# ControlVoltage.net
KiCad netlist of a schematic drawn in Altium Designer
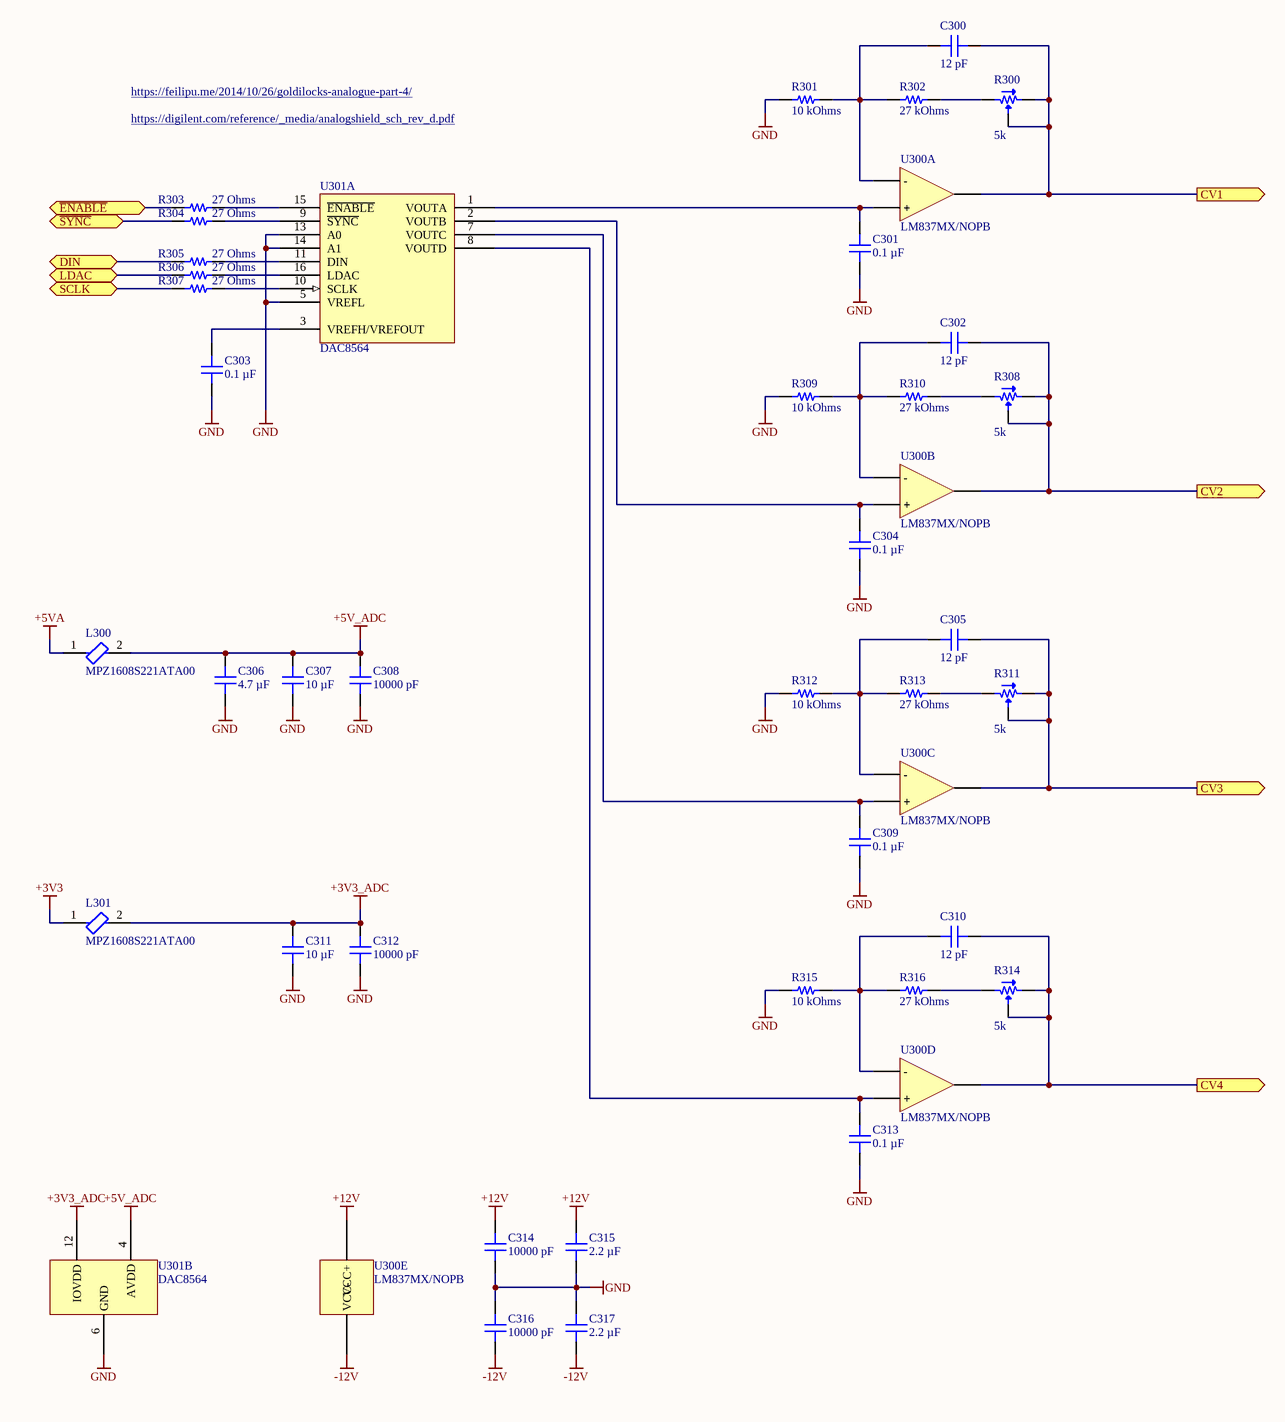
[diagram p0: ControlVoltage.SchDoc]

(export (version "E")
  (design (tool "Eeschema 10.0.6"))
  (components
    (comp (ref "C300")
      (value "12 pF")
      (footprint "CAP 0603_1608")
      (description "CAP CER 12PF 50V C0G/NPO 0603")
      (fields (field (name "PART NUMBER") "CC0603KRNPO9BN120") (field (name "MANUFACTURER") "Yageo"))
      (libsource (lib "Celestial Altium Library") (part "Capacitor"))
    )
    (comp (ref "C301")
      (value "0.1 µF")
      (footprint "CAP 0603_1608")
      (description "CAP CER 0.1UF 16V X7R 0603")
      (fields (field (name "PART NUMBER") "CS0603KRX7R7BB104") (field (name "MANUFACTURER") "Yageo"))
      (libsource (lib "Celestial Altium Library") (part "Capacitor"))
    )
    (comp (ref "C302")
      (value "12 pF")
      (footprint "CAP 0603_1608")
      (description "CAP CER 12PF 50V C0G/NPO 0603")
      (fields (field (name "PART NUMBER") "CC0603KRNPO9BN120") (field (name "MANUFACTURER") "Yageo"))
      (libsource (lib "Celestial Altium Library") (part "Capacitor"))
    )
    (comp (ref "C303")
      (value "0.1 µF")
      (footprint "CAP 0603_1608")
      (description "CAP CER 0.1UF 25V Y5V 0603")
      (fields (field (name "PART NUMBER") "CC0603MRY5V8BB104") (field (name "MANUFACTURER") "Yageo"))
      (libsource (lib "Celestial Altium Library") (part "Capacitor"))
    )
    (comp (ref "C304")
      (value "0.1 µF")
      (footprint "CAP 0603_1608")
      (description "CAP CER 0.1UF 16V X7R 0603")
      (fields (field (name "PART NUMBER") "CS0603KRX7R7BB104") (field (name "MANUFACTURER") "Yageo"))
      (libsource (lib "Celestial Altium Library") (part "Capacitor"))
    )
    (comp (ref "C305")
      (value "12 pF")
      (footprint "CAP 0603_1608")
      (description "CAP CER 12PF 50V C0G/NPO 0603")
      (fields (field (name "PART NUMBER") "CC0603KRNPO9BN120") (field (name "MANUFACTURER") "Yageo"))
      (libsource (lib "Celestial Altium Library") (part "Capacitor"))
    )
    (comp (ref "C306")
      (value "4.7 µF")
      (footprint "CAP 0603_1608")
      (description "CAP CER 4.7UF 10V X5R 0603")
      (fields (field (name "PART NUMBER") "CC0603MRX5R6BB475") (field (name "MANUFACTURER") "Yageo"))
      (libsource (lib "Celestial Altium Library") (part "Capacitor"))
    )
    (comp (ref "C307")
      (value "10 µF")
      (footprint "CAP 0603_1608")
      (description "CAP CER 10UF 4V X5R 0603")
      (fields (field (name "PART NUMBER") "CC0603MRX5R4BB106") (field (name "MANUFACTURER") "Yageo"))
      (libsource (lib "Celestial Altium Library") (part "Capacitor"))
    )
    (comp (ref "C308")
      (value "10000 pF")
      (footprint "CAP 0603_1608")
      (description "CAP CER 10000PF 50V X7R 0603")
      (fields (field (name "PART NUMBER") "CC0603JRX7R9BB103") (field (name "MANUFACTURER") "Yageo"))
      (libsource (lib "Celestial Altium Library") (part "Capacitor"))
    )
    (comp (ref "C309")
      (value "0.1 µF")
      (footprint "CAP 0603_1608")
      (description "CAP CER 0.1UF 16V X7R 0603")
      (fields (field (name "PART NUMBER") "CS0603KRX7R7BB104") (field (name "MANUFACTURER") "Yageo"))
      (libsource (lib "Celestial Altium Library") (part "Capacitor"))
    )
    (comp (ref "C310")
      (value "12 pF")
      (footprint "CAP 0603_1608")
      (description "CAP CER 12PF 50V C0G/NPO 0603")
      (fields (field (name "PART NUMBER") "CC0603KRNPO9BN120") (field (name "MANUFACTURER") "Yageo"))
      (libsource (lib "Celestial Altium Library") (part "Capacitor"))
    )
    (comp (ref "C311")
      (value "10 µF")
      (footprint "CAP 0603_1608")
      (description "CAP CER 10UF 4V X5R 0603")
      (fields (field (name "PART NUMBER") "CC0603MRX5R4BB106") (field (name "MANUFACTURER") "Yageo"))
      (libsource (lib "Celestial Altium Library") (part "Capacitor"))
    )
    (comp (ref "C312")
      (value "10000 pF")
      (footprint "CAP 0603_1608")
      (description "CAP CER 10000PF 50V X7R 0603")
      (fields (field (name "PART NUMBER") "CC0603JRX7R9BB103") (field (name "MANUFACTURER") "Yageo"))
      (libsource (lib "Celestial Altium Library") (part "Capacitor"))
    )
    (comp (ref "C313")
      (value "0.1 µF")
      (footprint "CAP 0603_1608")
      (description "CAP CER 0.1UF 16V X7R 0603")
      (fields (field (name "PART NUMBER") "CS0603KRX7R7BB104") (field (name "MANUFACTURER") "Yageo"))
      (libsource (lib "Celestial Altium Library") (part "Capacitor"))
    )
    (comp (ref "C314")
      (value "10000 pF")
      (footprint "CAP 0603_1608")
      (description "CAP CER 10000PF 50V X7R 0603")
      (fields (field (name "PART NUMBER") "CC0603JRX7R9BB103") (field (name "MANUFACTURER") "Yageo"))
      (libsource (lib "Celestial Altium Library") (part "Capacitor"))
    )
    (comp (ref "C315")
      (value "2.2 µF")
      (footprint "CAP 0603_1608")
      (description "CAP CER 2.2UF 16V Y5V 0603")
      (fields (field (name "PART NUMBER") "CC0603ZRY5V7BB225") (field (name "MANUFACTURER") "Yageo"))
      (libsource (lib "Celestial Altium Library") (part "Capacitor"))
    )
    (comp (ref "C316")
      (value "10000 pF")
      (footprint "CAP 0603_1608")
      (description "CAP CER 10000PF 50V X7R 0603")
      (fields (field (name "PART NUMBER") "CC0603JRX7R9BB103") (field (name "MANUFACTURER") "Yageo"))
      (libsource (lib "Celestial Altium Library") (part "Capacitor"))
    )
    (comp (ref "C317")
      (value "2.2 µF")
      (footprint "CAP 0603_1608")
      (description "CAP CER 2.2UF 16V Y5V 0603")
      (fields (field (name "PART NUMBER") "CC0603ZRY5V7BB225") (field (name "MANUFACTURER") "Yageo"))
      (libsource (lib "Celestial Altium Library") (part "Capacitor"))
    )
    (comp (ref "L300")
      (value "MPZ1608S221ATA00")
      (footprint "FP-MPZ1608-0_8-MFG")
      (description "Power line Ferrite Bead 220Ω @ 100MHz 2.2A DCR 0.05Ω SMD 0603")
      (fields (field (name "TOLERANCE") "25%"))
      (libsource (lib "Altium Content Vault") (part "5f30dd21d616792df468990f7003faa"))
    )
    (comp (ref "L301")
      (value "MPZ1608S221ATA00")
      (footprint "FP-MPZ1608-0_8-MFG")
      (description "Power line Ferrite Bead 220Ω @ 100MHz 2.2A DCR 0.05Ω SMD 0603")
      (fields (field (name "TOLERANCE") "25%"))
      (libsource (lib "Altium Content Vault") (part "5f30dd21d616792df468990f7003faa"))
    )
    (comp (ref "R300")
      (value "5k")
      (footprint "BOURNS_TRIM_3296")
      (description "Bourns Trimmer Resistor - Through Hole - Series 3296")
      (libsource (lib "LabratsSynthLib") (part "BOURNS_TRIM_POT_3296"))
    )
    (comp (ref "R301")
      (value "10 kOhms")
      (footprint "RES 0603_1608")
      (description "RES SMD 10K OHM 1% 1/10W 0603")
      (fields (field (name "PART NUMBER") "CRCW060310K0FKTA") (field (name "MANUFACTURER") "Vishay Dale"))
      (libsource (lib "Celestial Altium Library") (part "Resistor"))
    )
    (comp (ref "R302")
      (value "27 kOhms")
      (footprint "RES 0603_1608")
      (description "RES 24.9K OHM 1% 1/10W 0603")
      (fields (field (name "PART NUMBER") "CRCW060324K9FKEAC") (field (name "MANUFACTURER") "Vishay Dale"))
      (libsource (lib "Celestial Altium Library") (part "Resistor"))
    )
    (comp (ref "R303")
      (value "27 Ohms")
      (footprint "RES 0603_1608")
      (description "RES SMD 27 OHM 1% 1/10W 0603")
      (fields (field (name "PART NUMBER") "CRCW060327R0FKEA") (field (name "MANUFACTURER") "Vishay Dale"))
      (libsource (lib "Celestial Altium Library") (part "Resistor"))
    )
    (comp (ref "R304")
      (value "27 Ohms")
      (footprint "RES 0603_1608")
      (description "RES SMD 27 OHM 1% 1/10W 0603")
      (fields (field (name "PART NUMBER") "CRCW060327R0FKEA") (field (name "MANUFACTURER") "Vishay Dale"))
      (libsource (lib "Celestial Altium Library") (part "Resistor"))
    )
    (comp (ref "R305")
      (value "27 Ohms")
      (footprint "RES 0603_1608")
      (description "RES SMD 27 OHM 1% 1/10W 0603")
      (fields (field (name "PART NUMBER") "CRCW060327R0FKEA") (field (name "MANUFACTURER") "Vishay Dale"))
      (libsource (lib "Celestial Altium Library") (part "Resistor"))
    )
    (comp (ref "R306")
      (value "27 Ohms")
      (footprint "RES 0603_1608")
      (description "RES SMD 27 OHM 1% 1/10W 0603")
      (fields (field (name "PART NUMBER") "CRCW060327R0FKEA") (field (name "MANUFACTURER") "Vishay Dale"))
      (libsource (lib "Celestial Altium Library") (part "Resistor"))
    )
    (comp (ref "R307")
      (value "27 Ohms")
      (footprint "RES 0603_1608")
      (description "RES SMD 27 OHM 1% 1/10W 0603")
      (fields (field (name "PART NUMBER") "CRCW060327R0FKEA") (field (name "MANUFACTURER") "Vishay Dale"))
      (libsource (lib "Celestial Altium Library") (part "Resistor"))
    )
    (comp (ref "R308")
      (value "5k")
      (footprint "BOURNS_TRIM_3296")
      (description "Bourns Trimmer Resistor - Through Hole - Series 3296")
      (libsource (lib "LabratsSynthLib") (part "BOURNS_TRIM_POT_3296"))
    )
    (comp (ref "R309")
      (value "10 kOhms")
      (footprint "RES 0603_1608")
      (description "RES SMD 10K OHM 1% 1/10W 0603")
      (fields (field (name "PART NUMBER") "CRCW060310K0FKTA") (field (name "MANUFACTURER") "Vishay Dale"))
      (libsource (lib "Celestial Altium Library") (part "Resistor"))
    )
    (comp (ref "R310")
      (value "27 kOhms")
      (footprint "RES 0603_1608")
      (description "RES 24.9K OHM 1% 1/10W 0603")
      (fields (field (name "PART NUMBER") "CRCW060324K9FKEAC") (field (name "MANUFACTURER") "Vishay Dale"))
      (libsource (lib "Celestial Altium Library") (part "Resistor"))
    )
    (comp (ref "R311")
      (value "5k")
      (footprint "BOURNS_TRIM_3296")
      (description "Bourns Trimmer Resistor - Through Hole - Series 3296")
      (libsource (lib "LabratsSynthLib") (part "BOURNS_TRIM_POT_3296"))
    )
    (comp (ref "R312")
      (value "10 kOhms")
      (footprint "RES 0603_1608")
      (description "RES SMD 10K OHM 1% 1/10W 0603")
      (fields (field (name "PART NUMBER") "CRCW060310K0FKTA") (field (name "MANUFACTURER") "Vishay Dale"))
      (libsource (lib "Celestial Altium Library") (part "Resistor"))
    )
    (comp (ref "R313")
      (value "27 kOhms")
      (footprint "RES 0603_1608")
      (description "RES 24.9K OHM 1% 1/10W 0603")
      (fields (field (name "PART NUMBER") "CRCW060324K9FKEAC") (field (name "MANUFACTURER") "Vishay Dale"))
      (libsource (lib "Celestial Altium Library") (part "Resistor"))
    )
    (comp (ref "R314")
      (value "5k")
      (footprint "BOURNS_TRIM_3296")
      (description "Bourns Trimmer Resistor - Through Hole - Series 3296")
      (libsource (lib "LabratsSynthLib") (part "BOURNS_TRIM_POT_3296"))
    )
    (comp (ref "R315")
      (value "10 kOhms")
      (footprint "RES 0603_1608")
      (description "RES SMD 10K OHM 1% 1/10W 0603")
      (fields (field (name "PART NUMBER") "CRCW060310K0FKTA") (field (name "MANUFACTURER") "Vishay Dale"))
      (libsource (lib "Celestial Altium Library") (part "Resistor"))
    )
    (comp (ref "R316")
      (value "27 kOhms")
      (footprint "RES 0603_1608")
      (description "RES 24.9K OHM 1% 1/10W 0603")
      (fields (field (name "PART NUMBER") "CRCW060324K9FKEAC") (field (name "MANUFACTURER") "Vishay Dale"))
      (libsource (lib "Celestial Altium Library") (part "Resistor"))
    )
    (comp (ref "U300")
      (value "LM837MX/NOPB")
      (footprint "FP-D0014A-IPC_B")
      (description "IC OPAMP GP 4 CIRCUIT 14SOIC")
      (libsource (lib "LabratsSynthLib") (part "LM837MX/NOPB"))
    )
    (comp (ref "U301")
      (value "DAC8564")
      (footprint "SOP65P640X120-16N")
      (description "Digital to Analog Converters - DAC 16B Quad Ch Ultra-Lo Glitch Vltg Output")
      (libsource (lib "LabratsSynthLib") (part "DAC8564"))
    )
  )
  (nets
    (net (code "1") (name "+3V3") (class "Default")
      (node (ref "L301") (pin "1") (pinfunction "1_1") (pintype "passive"))
    )
    (net (code "2") (name "+3V3_ADC") (class "Default")
      (node (ref "C311") (pin "2") (pinfunction "2_2") (pintype "passive"))
      (node (ref "C312") (pin "2") (pinfunction "2_2") (pintype "passive"))
      (node (ref "L301") (pin "2") (pinfunction "2_2") (pintype "passive"))
      (node (ref "U301") (pin "12") (pinfunction "IOVDD_12") (pintype "power_in"))
    )
    (net (code "3") (name "+5VA") (class "Default")
      (node (ref "L300") (pin "1") (pinfunction "1_1") (pintype "passive"))
    )
    (net (code "4") (name "+5V_ADC") (class "Default")
      (node (ref "C306") (pin "2") (pinfunction "2_2") (pintype "passive"))
      (node (ref "C307") (pin "2") (pinfunction "2_2") (pintype "passive"))
      (node (ref "C308") (pin "2") (pinfunction "2_2") (pintype "passive"))
      (node (ref "L300") (pin "2") (pinfunction "2_2") (pintype "passive"))
      (node (ref "U301") (pin "4") (pinfunction "AVDD_4") (pintype "power_in"))
    )
    (net (code "5") (name "+12V") (class "Default")
      (node (ref "C314") (pin "2") (pinfunction "2_2") (pintype "passive"))
      (node (ref "C315") (pin "2") (pinfunction "2_2") (pintype "passive"))
      (node (ref "U300") (pin "4") (pinfunction "VCC+_4") (pintype "power_in"))
    )
    (net (code "6") (name "-12V") (class "Default")
      (node (ref "C316") (pin "1") (pinfunction "1_1") (pintype "passive"))
      (node (ref "C317") (pin "1") (pinfunction "1_1") (pintype "passive"))
      (node (ref "U300") (pin "11") (pinfunction "VCC-_11") (pintype "power_in"))
    )
    (net (code "7") (name "/CV1") (class "Default")
      (node (ref "C300") (pin "2") (pinfunction "2_2") (pintype "passive"))
      (node (ref "R300") (pin "2") (pinfunction "2_2") (pintype "passive"))
      (node (ref "R300") (pin "3") (pinfunction "3_3") (pintype "passive"))
      (node (ref "U300") (pin "1") (pinfunction "Output_1") (pintype "passive"))
    )
    (net (code "8") (name "/CV2") (class "Default")
      (node (ref "C302") (pin "2") (pinfunction "2_2") (pintype "passive"))
      (node (ref "R308") (pin "2") (pinfunction "2_2") (pintype "passive"))
      (node (ref "R308") (pin "3") (pinfunction "3_3") (pintype "passive"))
      (node (ref "U300") (pin "7") (pinfunction "Output_7") (pintype "passive"))
    )
    (net (code "9") (name "/CV3") (class "Default")
      (node (ref "C305") (pin "2") (pinfunction "2_2") (pintype "passive"))
      (node (ref "R311") (pin "2") (pinfunction "2_2") (pintype "passive"))
      (node (ref "R311") (pin "3") (pinfunction "3_3") (pintype "passive"))
      (node (ref "U300") (pin "8") (pinfunction "Output_8") (pintype "passive"))
    )
    (net (code "10") (name "/CV4") (class "Default")
      (node (ref "C310") (pin "2") (pinfunction "2_2") (pintype "passive"))
      (node (ref "R314") (pin "2") (pinfunction "2_2") (pintype "passive"))
      (node (ref "R314") (pin "3") (pinfunction "3_3") (pintype "passive"))
      (node (ref "U300") (pin "14") (pinfunction "Output_14") (pintype "passive"))
    )
    (net (code "11") (name "/DIN") (class "Default")
      (node (ref "R305") (pin "1") (pinfunction "1_1") (pintype "passive"))
    )
    (net (code "12") (name "/LDAC") (class "Default")
      (node (ref "R306") (pin "1") (pinfunction "1_1") (pintype "passive"))
    )
    (net (code "13") (name "/SCLK") (class "Default")
      (node (ref "R307") (pin "1") (pinfunction "1_1") (pintype "passive"))
    )
    (net (code "14") (name "/~{ENABLE}") (class "Default")
      (node (ref "R303") (pin "1") (pinfunction "1_1") (pintype "passive"))
    )
    (net (code "15") (name "/~{SYNC}") (class "Default")
      (node (ref "R304") (pin "1") (pinfunction "1_1") (pintype "passive"))
    )
    (net (code "16") (name "GND") (class "Default")
      (node (ref "C301") (pin "1") (pinfunction "1_1") (pintype "passive"))
      (node (ref "C303") (pin "1") (pinfunction "1_1") (pintype "passive"))
      (node (ref "C304") (pin "1") (pinfunction "1_1") (pintype "passive"))
      (node (ref "C306") (pin "1") (pinfunction "1_1") (pintype "passive"))
      (node (ref "C307") (pin "1") (pinfunction "1_1") (pintype "passive"))
      (node (ref "C308") (pin "1") (pinfunction "1_1") (pintype "passive"))
      (node (ref "C309") (pin "1") (pinfunction "1_1") (pintype "passive"))
      (node (ref "C311") (pin "1") (pinfunction "1_1") (pintype "passive"))
      (node (ref "C312") (pin "1") (pinfunction "1_1") (pintype "passive"))
      (node (ref "C313") (pin "1") (pinfunction "1_1") (pintype "passive"))
      (node (ref "C314") (pin "1") (pinfunction "1_1") (pintype "passive"))
      (node (ref "C315") (pin "1") (pinfunction "1_1") (pintype "passive"))
      (node (ref "C316") (pin "2") (pinfunction "2_2") (pintype "passive"))
      (node (ref "C317") (pin "2") (pinfunction "2_2") (pintype "passive"))
      (node (ref "R301") (pin "1") (pinfunction "1_1") (pintype "passive"))
      (node (ref "R309") (pin "1") (pinfunction "1_1") (pintype "passive"))
      (node (ref "R312") (pin "1") (pinfunction "1_1") (pintype "passive"))
      (node (ref "R315") (pin "1") (pinfunction "1_1") (pintype "passive"))
      (node (ref "U301") (pin "13") (pinfunction "A0_13") (pintype "passive"))
      (node (ref "U301") (pin "14") (pinfunction "A1_14") (pintype "passive"))
      (node (ref "U301") (pin "5") (pinfunction "VREFL_5") (pintype "passive"))
      (node (ref "U301") (pin "6") (pinfunction "GND_6") (pintype "power_in"))
    )
    (net (code "17") (name "Net-(R300-Pad1)") (class "Default")
      (node (ref "R300") (pin "1") (pinfunction "1_1") (pintype "passive"))
      (node (ref "R302") (pin "2") (pinfunction "2_2") (pintype "passive"))
    )
    (net (code "18") (name "Net-(R308-Pad1)") (class "Default")
      (node (ref "R308") (pin "1") (pinfunction "1_1") (pintype "passive"))
      (node (ref "R310") (pin "2") (pinfunction "2_2") (pintype "passive"))
    )
    (net (code "19") (name "Net-(R311-Pad1)") (class "Default")
      (node (ref "R311") (pin "1") (pinfunction "1_1") (pintype "passive"))
      (node (ref "R313") (pin "2") (pinfunction "2_2") (pintype "passive"))
    )
    (net (code "20") (name "Net-(R314-Pad1)") (class "Default")
      (node (ref "R314") (pin "1") (pinfunction "1_1") (pintype "passive"))
      (node (ref "R316") (pin "2") (pinfunction "2_2") (pintype "passive"))
    )
    (net (code "21") (name "Net-(U300A-+)") (class "Default")
      (node (ref "C301") (pin "2") (pinfunction "2_2") (pintype "passive"))
      (node (ref "U300") (pin "3") (pinfunction "+_3") (pintype "passive"))
      (node (ref "U301") (pin "1") (pinfunction "VOUTA_1") (pintype "passive"))
    )
    (net (code "22") (name "Net-(U300A--)") (class "Default")
      (node (ref "C300") (pin "1") (pinfunction "1_1") (pintype "passive"))
      (node (ref "R301") (pin "2") (pinfunction "2_2") (pintype "passive"))
      (node (ref "R302") (pin "1") (pinfunction "1_1") (pintype "passive"))
      (node (ref "U300") (pin "2") (pinfunction "-_2") (pintype "passive"))
    )
    (net (code "23") (name "Net-(U300B-+)") (class "Default")
      (node (ref "C304") (pin "2") (pinfunction "2_2") (pintype "passive"))
      (node (ref "U300") (pin "5") (pinfunction "+_5") (pintype "passive"))
      (node (ref "U301") (pin "2") (pinfunction "VOUTB_2") (pintype "passive"))
    )
    (net (code "24") (name "Net-(U300B--)") (class "Default")
      (node (ref "C302") (pin "1") (pinfunction "1_1") (pintype "passive"))
      (node (ref "R309") (pin "2") (pinfunction "2_2") (pintype "passive"))
      (node (ref "R310") (pin "1") (pinfunction "1_1") (pintype "passive"))
      (node (ref "U300") (pin "6") (pinfunction "-_6") (pintype "passive"))
    )
    (net (code "25") (name "Net-(U300C-+)") (class "Default")
      (node (ref "C309") (pin "2") (pinfunction "2_2") (pintype "passive"))
      (node (ref "U300") (pin "10") (pinfunction "+_10") (pintype "passive"))
      (node (ref "U301") (pin "7") (pinfunction "VOUTC_7") (pintype "passive"))
    )
    (net (code "26") (name "Net-(U300C--)") (class "Default")
      (node (ref "C305") (pin "1") (pinfunction "1_1") (pintype "passive"))
      (node (ref "R312") (pin "2") (pinfunction "2_2") (pintype "passive"))
      (node (ref "R313") (pin "1") (pinfunction "1_1") (pintype "passive"))
      (node (ref "U300") (pin "9") (pinfunction "-_9") (pintype "passive"))
    )
    (net (code "27") (name "Net-(U300D-+)") (class "Default")
      (node (ref "C313") (pin "2") (pinfunction "2_2") (pintype "passive"))
      (node (ref "U300") (pin "12") (pinfunction "+_12") (pintype "passive"))
      (node (ref "U301") (pin "8") (pinfunction "VOUTD_8") (pintype "passive"))
    )
    (net (code "28") (name "Net-(U300D--)") (class "Default")
      (node (ref "C310") (pin "1") (pinfunction "1_1") (pintype "passive"))
      (node (ref "R315") (pin "2") (pinfunction "2_2") (pintype "passive"))
      (node (ref "R316") (pin "1") (pinfunction "1_1") (pintype "passive"))
      (node (ref "U300") (pin "13") (pinfunction "-_13") (pintype "passive"))
    )
    (net (code "29") (name "Net-(U301A-DIN)") (class "Default")
      (node (ref "R305") (pin "2") (pinfunction "2_2") (pintype "passive"))
      (node (ref "U301") (pin "11") (pinfunction "DIN_11") (pintype "passive"))
    )
    (net (code "30") (name "Net-(U301A-LDAC)") (class "Default")
      (node (ref "R306") (pin "2") (pinfunction "2_2") (pintype "passive"))
      (node (ref "U301") (pin "16") (pinfunction "LDAC_16") (pintype "passive"))
    )
    (net (code "31") (name "Net-(U301A-SCLK)") (class "Default")
      (node (ref "R307") (pin "2") (pinfunction "2_2") (pintype "passive"))
      (node (ref "U301") (pin "10") (pinfunction "SCLK_10") (pintype "input"))
    )
    (net (code "32") (name "Net-(U301A-VREFH{slash}VREFOUT)") (class "Default")
      (node (ref "C303") (pin "2") (pinfunction "2_2") (pintype "passive"))
      (node (ref "U301") (pin "3") (pinfunction "VREFH/VREFOUT_3") (pintype "passive"))
    )
    (net (code "33") (name "Net-(U301A-~{ENABLE})") (class "Default")
      (node (ref "R303") (pin "2") (pinfunction "2_2") (pintype "passive"))
      (node (ref "U301") (pin "15") (pinfunction "~{ENABLE}_15") (pintype "passive"))
    )
    (net (code "34") (name "Net-(U301A-~{SYNC})") (class "Default")
      (node (ref "R304") (pin "2") (pinfunction "2_2") (pintype "passive"))
      (node (ref "U301") (pin "9") (pinfunction "~{SYNC}_9") (pintype "passive"))
    )
  )
)
